# STM32F446RE_board.net
KiCad netlist of a schematic drawn in Altium Designer
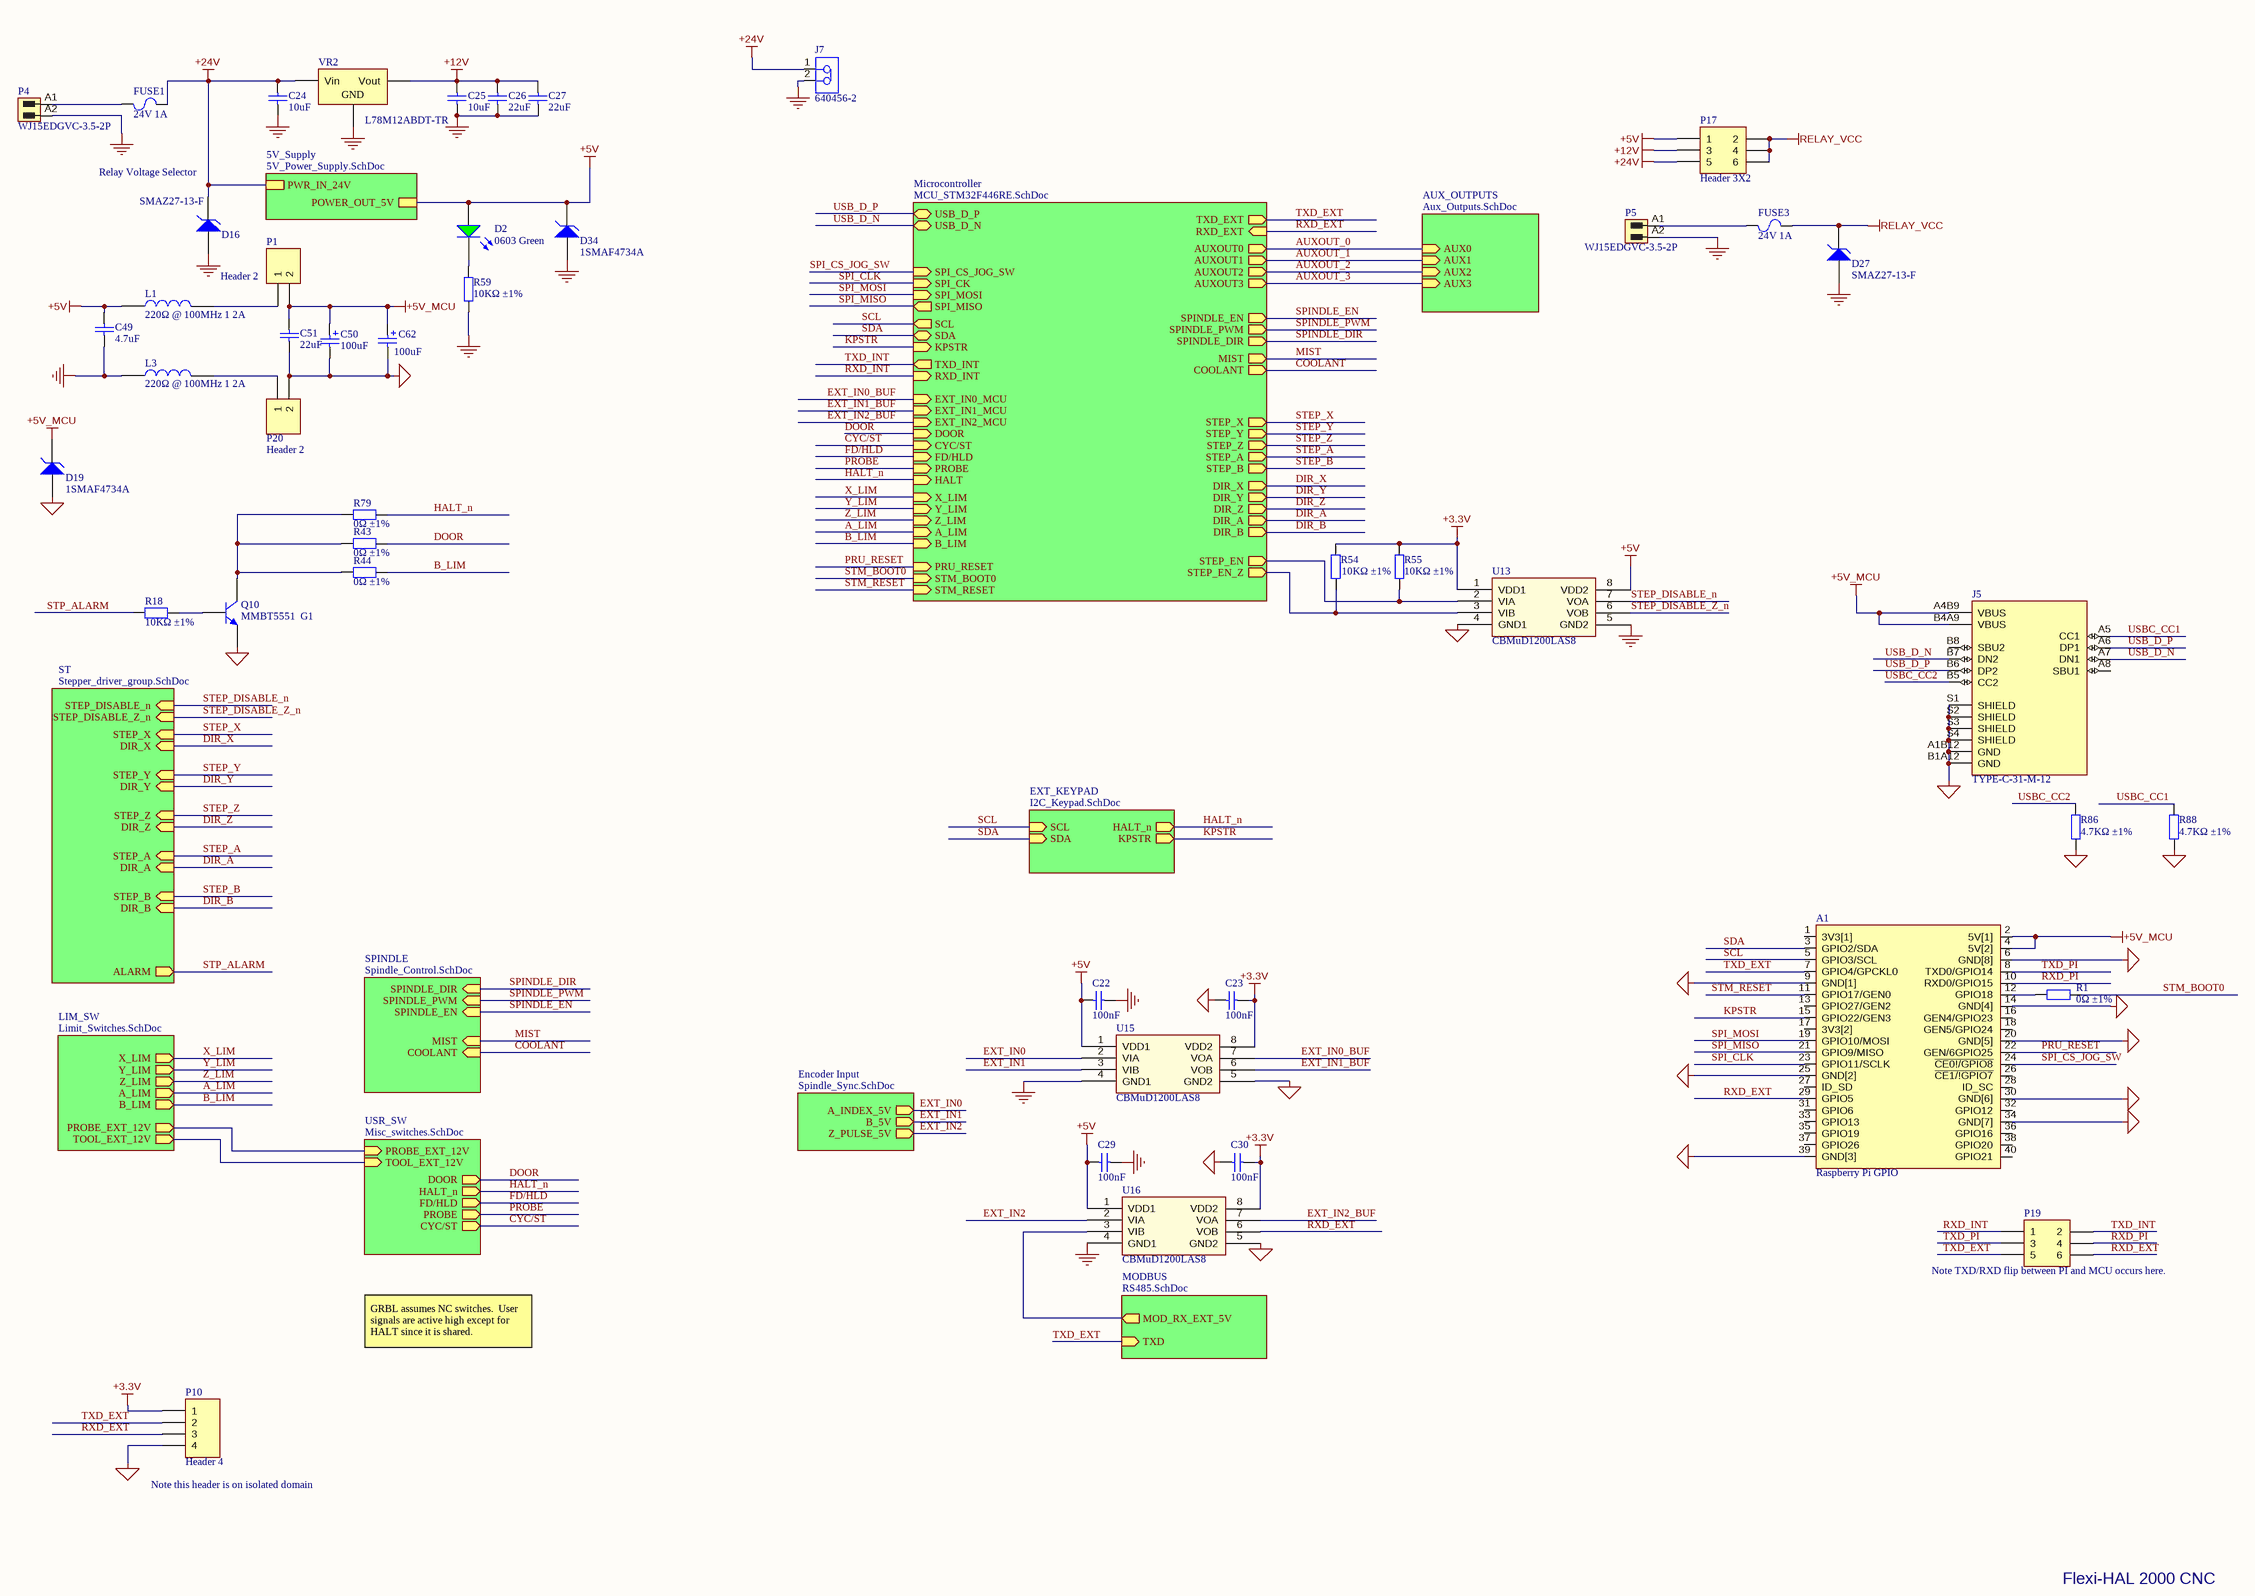
[diagram p0: STM32F446RE_board.SchDoc]

(export (version "E")
  (design (tool "Eeschema 10.0.6"))
  (components
    (comp (ref "A1")
      (value "Raspberry Pi GPIO")
      (footprint "MODULE_RASPBERRY_PI_4_MODEL_B")
      (description "Raspberry Pi Zero WH _Zero W with Headers_")
      (fields (field (name "MP") "DS1023-2*20SF11") (field (name "MF") "CONNFLY Elec"))
      (libsource (lib "Universal_CNC_Breakout") (part "ADA3708"))
    )
    (comp (ref "C22")
      (value "100nF")
      (footprint "0603_C")
      (description "Chip capacitors")
      (fields (field (name "MANUFACTURER") "YAGEO") (field (name "PARTNUMBER") "CC0603KRX7R9BB104"))
      (libsource (lib "Cap") (part "0603 100nF (104) 10% 50V"))
    )
    (comp (ref "C23")
      (value "100nF")
      (footprint "0603_C")
      (description "Chip capacitors")
      (fields (field (name "MANUFACTURER") "YAGEO") (field (name "PARTNUMBER") "CC0603KRX7R9BB104"))
      (libsource (lib "Cap") (part "0603 100nF (104) 10% 50V"))
    )
    (comp (ref "C24")
      (value "10uF")
      (footprint "1206_C")
      (description "Chip capacitors")
      (fields
        (field (name "MANUFACTURER") "Samsung Electro-Mechanics")
        (field (name "PARTNUMBER") "CL31A106KBHNNNE")
      )
      (libsource (lib "Cap") (part "1206 10uF (106) 10% 50V"))
    )
    (comp (ref "C25")
      (value "10uF")
      (footprint "1206_C")
      (description "Chip capacitors")
      (fields
        (field (name "MANUFACTURER") "Samsung Electro-Mechanics")
        (field (name "PARTNUMBER") "CL31A106KBHNNNE")
      )
      (libsource (lib "Cap") (part "1206 10uF (106) 10% 50V"))
    )
    (comp (ref "C26")
      (value "22uF")
      (footprint "0805_C")
      (description "Chip capacitors")
      (fields
        (field (name "MANUFACTURER") "Samsung Electro-Mechanics")
        (field (name "PARTNUMBER") "CL21A226MAQNNNE")
      )
      (libsource (lib "Cap") (part "0805 22uF (226) 20% 25V"))
    )
    (comp (ref "C27")
      (value "22uF")
      (footprint "0805_C")
      (description "Chip capacitors")
      (fields
        (field (name "MANUFACTURER") "Samsung Electro-Mechanics")
        (field (name "PARTNUMBER") "CL21A226MAQNNNE")
      )
      (libsource (lib "Cap") (part "0805 22uF (226) 20% 25V"))
    )
    (comp (ref "C29")
      (value "100nF")
      (footprint "0603_C")
      (description "Chip capacitors")
      (fields (field (name "MANUFACTURER") "YAGEO") (field (name "PARTNUMBER") "CC0603KRX7R9BB104"))
      (libsource (lib "Cap") (part "0603 100nF (104) 10% 50V"))
    )
    (comp (ref "C30")
      (value "100nF")
      (footprint "0603_C")
      (description "Chip capacitors")
      (fields (field (name "MANUFACTURER") "YAGEO") (field (name "PARTNUMBER") "CC0603KRX7R9BB104"))
      (libsource (lib "Cap") (part "0603 100nF (104) 10% 50V"))
    )
    (comp (ref "C49")
      (value "4.7uF")
      (footprint "0603_C")
      (description "Chip capacitors")
      (fields
        (field (name "MANUFACTURER") "Samsung Electro-Mechanics")
        (field (name "PARTNUMBER") "CL10A475KO8NNNC")
      )
      (libsource (lib "Cap") (part "0603 4.7uF (475) 10% 16V"))
    )
    (comp (ref "C50")
      (value "100uF")
      (footprint "CASE-B_3528")
      (description "Tantalum capacitor")
      (fields (field (name "MANUFACTURER") "AVX") (field (name "PARTNUMBER") "TAJB107K006RNJ"))
      (libsource (lib "Cap") (part "3528 100uF (107) 10% 6.3V"))
    )
    (comp (ref "C51")
      (value "22uF")
      (footprint "0805_C")
      (description "Chip capacitors")
      (fields
        (field (name "MANUFACTURER") "Samsung Electro-Mechanics")
        (field (name "PARTNUMBER") "CL21A226MAQNNNE")
      )
      (libsource (lib "Cap") (part "0805 22uF (226) 20% 25V"))
    )
    (comp (ref "C62")
      (value "100uF")
      (footprint "WCAP-ASLI_D6.3H7.7")
      (fields (field (name "MANUFACTURER") "Capxon International Elec"))
      (libsource (lib "IQAnalog") (part "865080445010"))
    )
    (comp (ref "D2")
      (value "0603 Green")
      (footprint "0603_LED_S1")
      (description "LED")
      (libsource (lib "LED") (part "0603 LED Green"))
    )
    (comp (ref "D16")
      (value "SMAZ27-13-F")
      (footprint "DIOM5226X240N")
      (description "27V ±5% 1W 500nA @ 20.5V SMA(DO-214AC) Zener Diodes RoHS")
      (libsource (lib "PrintNC_GRBLHAL_Breakout") (part "BZT52C27"))
    )
    (comp (ref "D19")
      (value "1SMAF4734A")
      (footprint "DIOM5226X240N")
      (description "27V ±5% 1W 500nA @ 20.5V SMA(DO-214AC) Zener Diodes RoHS")
      (libsource (lib "PrintNC_GRBLHAL_Breakout") (part "BZT52C27"))
    )
    (comp (ref "D27")
      (value "SMAZ27-13-F")
      (footprint "DIOM5226X240N")
      (description "27V ±5% 1W 500nA @ 20.5V SMA(DO-214AC) Zener Diodes RoHS")
      (libsource (lib "PrintNC_GRBLHAL_Breakout") (part "BZT52C27"))
    )
    (comp (ref "D34")
      (value "1SMAF4734A")
      (footprint "DIOM5226X240N")
      (description "27V ±5% 1W 500nA @ 20.5V SMA(DO-214AC) Zener Diodes RoHS")
      (libsource (lib "PrintNC_GRBLHAL_Breakout") (part "BZT52C27"))
    )
    (comp (ref "FUSE1")
      (value "24V 1A")
      (footprint "1206_C")
      (description "24V 1A 0.1s 1206 PTC Resettable Fuses RoHS")
      (fields
        (field (name "MANUFACTURER") "Jinrui Electronic Materials Co.")
        (field (name "PARTNUMBER") "JK-nSMD050-24")
      )
      (libsource (lib "PrintNC_GRBLHAL_Breakout") (part "JK-nSMD050-24"))
    )
    (comp (ref "FUSE3")
      (value "24V 1A")
      (footprint "1206_C")
      (description "24V 1A 0.1s 1206 PTC Resettable Fuses RoHS")
      (fields
        (field (name "MANUFACTURER") "Jinrui Electronic Materials Co.")
        (field (name "PARTNUMBER") "JK-nSMD050-24")
      )
      (libsource (lib "PrintNC_GRBLHAL_Breakout") (part "JK-nSMD050-24"))
    )
    (comp (ref "J5")
      (value "TYPE-C-31-M-12")
      (footprint "HRO_TYPE-C-31-M-12")
      (description "USB Connectors 24 Receptacle 1 8.94*7.3mm RoHS")
      (fields (field (name "MF") "HRO Electronics Co., Ltd."))
      (libsource (lib "Universal_CNC_Breakout") (part "TYPE-C-31-M-12"))
    )
    (comp (ref "J7")
      (value "640456-2")
      (footprint "TECO-640456-2_V")
      (fields (field (name "MANUFACTURER") "TE Connectivity"))
      (libsource (lib "Altium Content Vault") (part "CN-2P-F-QF2"))
    )
    (comp (ref "L1")
      (value "220Ω @ 100MHz 1 2A")
      (footprint "0805_C")
      (description "220Ω @ 100MHz 1 2A 150mΩ 0805 Ferrite Beads ROHS")
      (libsource (lib "FBEAD") (part "0402 220R@100Mhz 0.1A"))
    )
    (comp (ref "L3")
      (value "220Ω @ 100MHz 1 2A")
      (footprint "0805_C")
      (description "220Ω @ 100MHz 1 2A 150mΩ 0805 Ferrite Beads ROHS")
      (libsource (lib "FBEAD") (part "0402 220R@100Mhz 0.1A"))
    )
    (comp (ref "P1")
      (value "Header 2")
      (footprint "HDR1X2")
      (description "Header, 2-Pin")
      (fields (field (name "PUBLISHER") "Altium Limited"))
      (libsource (lib "") (part "Header 2_1"))
    )
    (comp (ref "P4")
      (value "WJ15EDGVC-3.5-2P")
      (footprint "691321100002")
      (libsource (lib "Universal_CNC_Breakout") (part "3.5mm Terminal Header 2p"))
    )
    (comp (ref "P5")
      (value "WJ15EDGVC-3.5-2P")
      (footprint "691321100002")
      (fields (field (name "MANUFACTURER") "Weidmueller"))
      (libsource (lib "Universal_CNC_Breakout") (part "3.5mm Terminal Header 2p"))
    )
    (comp (ref "P10")
      (value "Header 4")
      (footprint "HDR1X4")
      (description "Header, 4-Pin")
      (libsource (lib "Miscellaneous Connectors") (part "Header 4"))
    )
    (comp (ref "P17")
      (value "Header 3X2")
      (footprint "HDR2X3")
      (description "Header, 3-Pin, Dual row")
      (fields (field (name "PUBLISHER") "Altium Limited"))
      (libsource (lib "Miscellaneous Connectors") (part "Header 3X2"))
    )
    (comp (ref "P19")
      (value "Header 3X2")
      (footprint "HDR2X3")
      (description "Header, 3-Pin, Dual row")
      (fields (field (name "PUBLISHER") "Altium Limited"))
      (libsource (lib "Miscellaneous Connectors") (part "Header 3X2"))
    )
    (comp (ref "P20")
      (value "Header 2")
      (footprint "HDR1X2")
      (description "Header, 2-Pin")
      (fields (field (name "PUBLISHER") "Altium Limited"))
      (libsource (lib "Miscellaneous Connectors") (part "Header 2"))
    )
    (comp (ref "Q10")
      (value "MMBT5551  G1")
      (footprint "SOT-23(SOT-23-3)")
      (description "三极管")
      (libsource (lib "PrintNC_GRBLHAL_Breakout") (part "SOT-23 MMBT5551  G1"))
    )
    (comp (ref "R1")
      (value "0Ω ±1%")
      (footprint "0603_R")
      (description "Chip resistor")
      (fields (field (name "MANUFACTURER") "Uniroyal Elec") (field (name "PARTNUMBER") "0603WAF0000T5E"))
      (libsource (lib "RES") (part "0603 0R (0R0) 1%"))
    )
    (comp (ref "R18")
      (value "10KΩ ±1%")
      (footprint "0603_R")
      (description "Chip resistor")
      (fields (field (name "MANUFACTURER") "Uniroyal Elec") (field (name "PARTNUMBER") "0603WAF1002T5E"))
      (libsource (lib "") (part "0603 10K (1002) 1%_2"))
    )
    (comp (ref "R43")
      (value "0Ω ±1%")
      (footprint "0603_R")
      (description "Chip resistor")
      (fields (field (name "MANUFACTURER") "Uniroyal Elec") (field (name "PARTNUMBER") "0603WAF0000T5E"))
      (libsource (lib "RES") (part "0603 0R (0R0) 1%"))
    )
    (comp (ref "R44")
      (value "0Ω ±1%")
      (footprint "0603_R")
      (description "Chip resistor")
      (fields (field (name "MANUFACTURER") "Uniroyal Elec") (field (name "PARTNUMBER") "0603WAF0000T5E"))
      (libsource (lib "RES") (part "0603 0R (0R0) 1%"))
    )
    (comp (ref "R54")
      (value "10KΩ ±1%")
      (footprint "0603_R")
      (description "Chip resistor")
      (fields (field (name "MANUFACTURER") "Uniroyal Elec") (field (name "PARTNUMBER") "0603WAF1002T5E"))
      (libsource (lib "RES") (part "0603 10K (1002) 1%"))
    )
    (comp (ref "R55")
      (value "10KΩ ±1%")
      (footprint "0603_R")
      (description "Chip resistor")
      (fields (field (name "MANUFACTURER") "Uniroyal Elec") (field (name "PARTNUMBER") "0603WAF1002T5E"))
      (libsource (lib "RES") (part "0603 10K (1002) 1%"))
    )
    (comp (ref "R59")
      (value "10KΩ ±1%")
      (footprint "0603_R")
      (description "Chip resistor")
      (fields (field (name "MANUFACTURER") "Uniroyal Elec") (field (name "PARTNUMBER") "0603WAF1002T5E"))
      (libsource (lib "") (part "0603 10K (1002) 1%_1"))
    )
    (comp (ref "R79")
      (value "0Ω ±1%")
      (footprint "0603_R")
      (description "Chip resistor")
      (fields (field (name "MANUFACTURER") "Uniroyal Elec") (field (name "PARTNUMBER") "0603WAF0000T5E"))
      (libsource (lib "RES") (part "0603 0R (0R0) 1%"))
    )
    (comp (ref "R86")
      (value "4.7KΩ ±1%")
      (footprint "0603_R")
      (description "Chip resistor")
      (fields (field (name "MANUFACTURER") "Uniroyal Elec") (field (name "PARTNUMBER") "0603WAF4701T5E"))
      (libsource (lib "RES") (part "0603 4.7K (4701) 1%"))
    )
    (comp (ref "R88")
      (value "4.7KΩ ±1%")
      (footprint "0603_R")
      (description "Chip resistor")
      (fields (field (name "MANUFACTURER") "Uniroyal Elec") (field (name "PARTNUMBER") "0603WAF4701T5E"))
      (libsource (lib "RES") (part "0603 4.7K (4701) 1%"))
    )
    (comp (ref "U13")
      (value "CBMuD1200LAS8")
      (footprint "SOIC-8_150mil")
      (description "Dual Channel Isolator")
      (libsource (lib "IC") (part "CBMuD1200LAS8"))
    )
    (comp (ref "U15")
      (value "CBMuD1200LAS8")
      (footprint "SOIC-8_150mil")
      (description "Dual Channel Isolator")
      (libsource (lib "IC") (part "CBMuD1200LAS8"))
    )
    (comp (ref "U16")
      (value "CBMuD1200LAS8")
      (footprint "SOIC-8_150mil")
      (description "Dual Channel Isolator")
      (libsource (lib "IC") (part "CBMuD1200LAS8"))
    )
    (comp (ref "VR2")
      (value "L78M12ABDT-TR")
      (footprint "TO-252-2-180")
      (libsource (lib "PrintNC_GRBLHAL_Breakout") (part "TO-252-2 L78M05ABDT-TR"))
    )
  )
  (nets
    (net (code "1") (name "+3.3V") (class "Default")
      (node (ref "C23") (pin "2") (pinfunction "2_2") (pintype "passive"))
      (node (ref "C30") (pin "2") (pinfunction "2_2") (pintype "passive"))
      (node (ref "P10") (pin "1") (pinfunction "1_1") (pintype "passive"))
      (node (ref "R54") (pin "1") (pinfunction "1_1") (pintype "passive"))
      (node (ref "R55") (pin "1") (pinfunction "1_1") (pintype "passive"))
      (node (ref "U13") (pin "1") (pinfunction "VDD1_1") (pintype "passive"))
      (node (ref "U15") (pin "8") (pinfunction "VDD2_8") (pintype "passive"))
      (node (ref "U16") (pin "8") (pinfunction "VDD2_8") (pintype "passive"))
    )
    (net (code "2") (name "+5V") (class "Default")
      (node (ref "C22") (pin "1") (pinfunction "1_1") (pintype "passive"))
      (node (ref "C29") (pin "1") (pinfunction "1_1") (pintype "passive"))
      (node (ref "C49") (pin "2") (pinfunction "2_2") (pintype "passive"))
      (node (ref "D2") (pin "A") (pinfunction "A_A") (pintype "passive"))
      (node (ref "D34") (pin "2") (pinfunction "K_2") (pintype "passive"))
      (node (ref "L1") (pin "1") (pinfunction "1_1") (pintype "passive"))
      (node (ref "P17") (pin "1") (pinfunction "1_1") (pintype "passive"))
      (node (ref "U13") (pin "8") (pinfunction "VDD2_8") (pintype "passive"))
      (node (ref "U15") (pin "1") (pinfunction "VDD1_1") (pintype "passive"))
      (node (ref "U16") (pin "1") (pinfunction "VDD1_1") (pintype "passive"))
    )
    (net (code "3") (name "+5V_MCU") (class "Default")
      (node (ref "A1") (pin "2") (pinfunction "5V[1]_2") (pintype "power_in"))
      (node (ref "A1") (pin "4") (pinfunction "5V[2]_4") (pintype "power_in"))
      (node (ref "C50") (pin "1") (pinfunction "1_1") (pintype "passive"))
      (node (ref "C51") (pin "2") (pinfunction "2_2") (pintype "passive"))
      (node (ref "C62") (pin "1") (pinfunction "P_1") (pintype "passive"))
      (node (ref "D19") (pin "2") (pinfunction "K_2") (pintype "passive"))
      (node (ref "J5") (pin "A4B9") (pinfunction "VBUS_A4B9") (pintype "power_in"))
      (node (ref "J5") (pin "B4A9") (pinfunction "VBUS_B4A9") (pintype "power_in"))
      (node (ref "P1") (pin "2") (pinfunction "2_2") (pintype "passive"))
    )
    (net (code "4") (name "+12V") (class "Default")
      (node (ref "C25") (pin "2") (pinfunction "2_2") (pintype "passive"))
      (node (ref "C26") (pin "2") (pinfunction "2_2") (pintype "passive"))
      (node (ref "C27") (pin "2") (pinfunction "2_2") (pintype "passive"))
      (node (ref "P17") (pin "3") (pinfunction "3_3") (pintype "passive"))
      (node (ref "VR2") (pin "3") (pinfunction "Vout_3") (pintype "passive"))
    )
    (net (code "5") (name "+24V") (class "Default")
      (node (ref "C24") (pin "2") (pinfunction "2_2") (pintype "passive"))
      (node (ref "D16") (pin "2") (pinfunction "K_2") (pintype "passive"))
      (node (ref "FUSE1") (pin "2") (pinfunction "2_2") (pintype "passive"))
      (node (ref "J7") (pin "1") (pinfunction "1_1") (pintype "passive"))
      (node (ref "P17") (pin "5") (pinfunction "5_5") (pintype "passive"))
      (node (ref "VR2") (pin "1") (pinfunction "Vin_1") (pintype "passive"))
    )
    (net (code "11") (name "/B_LIM") (class "Default")
      (node (ref "R44") (pin "1") (pinfunction "1_1") (pintype "passive"))
    )
    (net (code "19") (name "/DOOR") (class "Default")
      (node (ref "R43") (pin "1") (pinfunction "1_1") (pintype "passive"))
    )
    (net (code "20") (name "/EXT_IN0") (class "Default")
      (node (ref "U15") (pin "2") (pinfunction "VIA_2") (pintype "passive"))
    )
    (net (code "21") (name "/EXT_IN0_BUF") (class "Default")
      (node (ref "U15") (pin "7") (pinfunction "VOA_7") (pintype "passive"))
    )
    (net (code "22") (name "/EXT_IN1") (class "Default")
      (node (ref "U15") (pin "3") (pinfunction "VIB_3") (pintype "passive"))
    )
    (net (code "23") (name "/EXT_IN1_BUF") (class "Default")
      (node (ref "U15") (pin "6") (pinfunction "VOB_6") (pintype "passive"))
    )
    (net (code "24") (name "/EXT_IN2") (class "Default")
      (node (ref "U16") (pin "2") (pinfunction "VIA_2") (pintype "passive"))
    )
    (net (code "25") (name "/EXT_IN2_BUF") (class "Default")
      (node (ref "U16") (pin "7") (pinfunction "VOA_7") (pintype "passive"))
    )
    (net (code "27") (name "/HALT_n") (class "Default")
      (node (ref "R79") (pin "1") (pinfunction "1_1") (pintype "passive"))
    )
    (net (code "28") (name "/KPSTR") (class "Default")
      (node (ref "A1") (pin "15") (pinfunction "GPIO22/GEN3_15") (pintype "bidirectional"))
    )
    (net (code "30") (name "/MOD_RX_EXT_5V") (class "Default")
      (node (ref "U16") (pin "3") (pinfunction "VIB_3") (pintype "passive"))
    )
    (net (code "33") (name "/PRU_RESET") (class "Default")
      (node (ref "A1") (pin "22") (pinfunction "GEN/6GPIO25_22") (pintype "bidirectional"))
    )
    (net (code "34") (name "/RXD_EXT") (class "Default")
      (node (ref "A1") (pin "29") (pinfunction "GPIO5_29") (pintype "bidirectional"))
      (node (ref "P10") (pin "3") (pinfunction "3_3") (pintype "passive"))
      (node (ref "P19") (pin "6") (pinfunction "6_6") (pintype "passive"))
      (node (ref "U16") (pin "6") (pinfunction "VOB_6") (pintype "passive"))
    )
    (net (code "35") (name "/RXD_INT") (class "Default")
      (node (ref "P19") (pin "1") (pinfunction "1_1") (pintype "passive"))
    )
    (net (code "36") (name "/RXD_PI") (class "Default")
      (node (ref "A1") (pin "10") (pinfunction "RXD0/GPIO15_10") (pintype "bidirectional"))
      (node (ref "P19") (pin "4") (pinfunction "4_4") (pintype "passive"))
    )
    (net (code "37") (name "/SCL") (class "Default")
      (node (ref "A1") (pin "5") (pinfunction "GPIO3/SCL_5") (pintype "bidirectional"))
    )
    (net (code "38") (name "/SDA") (class "Default")
      (node (ref "A1") (pin "3") (pinfunction "GPIO2/SDA_3") (pintype "bidirectional"))
    )
    (net (code "42") (name "/SPI_CLK") (class "Default")
      (node (ref "A1") (pin "23") (pinfunction "GPIO11/SCLK_23") (pintype "bidirectional"))
    )
    (net (code "43") (name "/SPI_CS_JOG_SW") (class "Default")
      (node (ref "A1") (pin "24") (pinfunction "~{CE0!/GPIO8}_24") (pintype "bidirectional"))
    )
    (net (code "44") (name "/SPI_MISO") (class "Default")
      (node (ref "A1") (pin "21") (pinfunction "GPIO9/MISO_21") (pintype "bidirectional"))
    )
    (net (code "45") (name "/SPI_MOSI") (class "Default")
      (node (ref "A1") (pin "19") (pinfunction "GPIO10/MOSI_19") (pintype "bidirectional"))
    )
    (net (code "48") (name "/STEP_DISABLE_Z_n") (class "Default")
      (node (ref "U13") (pin "6") (pinfunction "VOB_6") (pintype "passive"))
    )
    (net (code "49") (name "/STEP_DISABLE_n") (class "Default")
      (node (ref "U13") (pin "7") (pinfunction "VOA_7") (pintype "passive"))
    )
    (net (code "50") (name "/STEP_EN") (class "Default")
      (node (ref "R55") (pin "2") (pinfunction "2_2") (pintype "passive"))
      (node (ref "U13") (pin "2") (pinfunction "VIA_2") (pintype "passive"))
    )
    (net (code "51") (name "/STEP_EN_Z") (class "Default")
      (node (ref "R54") (pin "2") (pinfunction "2_2") (pintype "passive"))
      (node (ref "U13") (pin "3") (pinfunction "VIB_3") (pintype "passive"))
    )
    (net (code "55") (name "/STM_BOOT0") (class "Default")
      (node (ref "R1") (pin "1") (pinfunction "1_1") (pintype "passive"))
    )
    (net (code "56") (name "/STM_RESET") (class "Default")
      (node (ref "A1") (pin "11") (pinfunction "GPIO17/GEN0_11") (pintype "bidirectional"))
    )
    (net (code "57") (name "/STP_ALARM") (class "Default")
      (node (ref "R18") (pin "2") (pinfunction "2_2") (pintype "passive"))
    )
    (net (code "59") (name "/TXD_EXT") (class "Default")
      (node (ref "A1") (pin "7") (pinfunction "GPIO4/GPCKL0_7") (pintype "bidirectional"))
      (node (ref "P10") (pin "2") (pinfunction "2_2") (pintype "passive"))
      (node (ref "P19") (pin "5") (pinfunction "5_5") (pintype "passive"))
    )
    (net (code "60") (name "/TXD_INT") (class "Default")
      (node (ref "P19") (pin "2") (pinfunction "2_2") (pintype "passive"))
    )
    (net (code "61") (name "/TXD_PI") (class "Default")
      (node (ref "A1") (pin "8") (pinfunction "TXD0/GPIO14_8") (pintype "bidirectional"))
      (node (ref "P19") (pin "3") (pinfunction "3_3") (pintype "passive"))
    )
    (net (code "62") (name "/USBC_CC1") (class "Default")
      (node (ref "J5") (pin "A5") (pinfunction "CC1_A5") (pintype "bidirectional"))
      (node (ref "R88") (pin "1") (pinfunction "1_1") (pintype "passive"))
    )
    (net (code "63") (name "/USBC_CC2") (class "Default")
      (node (ref "J5") (pin "B5") (pinfunction "CC2_B5") (pintype "bidirectional"))
      (node (ref "R86") (pin "1") (pinfunction "1_1") (pintype "passive"))
    )
    (net (code "64") (name "/USB_D_N") (class "Default")
      (node (ref "J5") (pin "A7") (pinfunction "DN1_A7") (pintype "bidirectional"))
      (node (ref "J5") (pin "B7") (pinfunction "DN2_B7") (pintype "bidirectional"))
    )
    (net (code "65") (name "/USB_D_P") (class "Default")
      (node (ref "J5") (pin "A6") (pinfunction "DP1_A6") (pintype "bidirectional"))
      (node (ref "J5") (pin "B6") (pinfunction "DP2_B6") (pintype "bidirectional"))
    )
    (net (code "69") (name "GND") (class "Default")
      (node (ref "C22") (pin "2") (pinfunction "2_2") (pintype "passive"))
      (node (ref "C24") (pin "1") (pinfunction "1_1") (pintype "passive"))
      (node (ref "C25") (pin "1") (pinfunction "1_1") (pintype "passive"))
      (node (ref "C26") (pin "1") (pinfunction "1_1") (pintype "passive"))
      (node (ref "C27") (pin "1") (pinfunction "1_1") (pintype "passive"))
      (node (ref "C29") (pin "2") (pinfunction "2_2") (pintype "passive"))
      (node (ref "C49") (pin "1") (pinfunction "1_1") (pintype "passive"))
      (node (ref "D16") (pin "1") (pinfunction "A_1") (pintype "passive"))
      (node (ref "D27") (pin "1") (pinfunction "A_1") (pintype "passive"))
      (node (ref "D34") (pin "1") (pinfunction "A_1") (pintype "passive"))
      (node (ref "J7") (pin "2") (pinfunction "2_2") (pintype "passive"))
      (node (ref "L3") (pin "1") (pinfunction "1_1") (pintype "passive"))
      (node (ref "P4") (pin "A2") (pinfunction "A2_A2") (pintype "passive"))
      (node (ref "P5") (pin "A2") (pinfunction "A2_A2") (pintype "passive"))
      (node (ref "R59") (pin "1") (pinfunction "1_1") (pintype "passive"))
      (node (ref "U13") (pin "5") (pinfunction "GND2_5") (pintype "passive"))
      (node (ref "U15") (pin "4") (pinfunction "GND1_4") (pintype "passive"))
      (node (ref "U16") (pin "4") (pinfunction "GND1_4") (pintype "passive"))
      (node (ref "VR2") (pin "2") (pinfunction "GND_2") (pintype "passive"))
    )
    (net (code "70") (name "MCU_GND") (class "Default")
      (node (ref "A1") (pin "14") (pinfunction "GND[4]_14") (pintype "power_in"))
      (node (ref "A1") (pin "20") (pinfunction "GND[5]_20") (pintype "power_in"))
      (node (ref "A1") (pin "25") (pinfunction "GND[2]_25") (pintype "power_in"))
      (node (ref "A1") (pin "30") (pinfunction "GND[6]_30") (pintype "power_in"))
      (node (ref "A1") (pin "34") (pinfunction "GND[7]_34") (pintype "power_in"))
      (node (ref "A1") (pin "39") (pinfunction "GND[3]_39") (pintype "power_in"))
      (node (ref "A1") (pin "6") (pinfunction "GND[8]_6") (pintype "power_in"))
      (node (ref "A1") (pin "9") (pinfunction "GND[1]_9") (pintype "power_in"))
      (node (ref "C23") (pin "1") (pinfunction "1_1") (pintype "passive"))
      (node (ref "C30") (pin "1") (pinfunction "1_1") (pintype "passive"))
      (node (ref "C50") (pin "2") (pinfunction "2_2") (pintype "passive"))
      (node (ref "C51") (pin "1") (pinfunction "1_1") (pintype "passive"))
      (node (ref "C62") (pin "2") (pinfunction "N_2") (pintype "passive"))
      (node (ref "D19") (pin "1") (pinfunction "A_1") (pintype "passive"))
      (node (ref "J5") (pin "A1B12") (pinfunction "GND_A1B12") (pintype "power_in"))
      (node (ref "J5") (pin "B1A12") (pinfunction "GND_B1A12") (pintype "power_in"))
      (node (ref "J5") (pin "S1") (pinfunction "SHIELD_S1") (pintype "passive"))
      (node (ref "J5") (pin "S2") (pinfunction "SHIELD_S2") (pintype "passive"))
      (node (ref "J5") (pin "S3") (pinfunction "SHIELD_S3") (pintype "passive"))
      (node (ref "J5") (pin "S4") (pinfunction "SHIELD_S4") (pintype "passive"))
      (node (ref "P10") (pin "4") (pinfunction "4_4") (pintype "passive"))
      (node (ref "P20") (pin "2") (pinfunction "2_2") (pintype "passive"))
      (node (ref "Q10") (pin "2") (pinfunction "E_2") (pintype "passive"))
      (node (ref "R86") (pin "2") (pinfunction "2_2") (pintype "passive"))
      (node (ref "R88") (pin "2") (pinfunction "2_2") (pintype "passive"))
      (node (ref "U13") (pin "4") (pinfunction "GND1_4") (pintype "passive"))
      (node (ref "U15") (pin "5") (pinfunction "GND2_5") (pintype "passive"))
      (node (ref "U16") (pin "5") (pinfunction "GND2_5") (pintype "passive"))
    )
    (net (code "71") (name "Net-(A1-GPIO18)") (class "Default")
      (node (ref "A1") (pin "12") (pinfunction "GPIO18_12") (pintype "bidirectional"))
      (node (ref "R1") (pin "2") (pinfunction "2_2") (pintype "passive"))
    )
    (net (code "72") (name "Net-(D2-PadK)") (class "Default")
      (node (ref "D2") (pin "K") (pinfunction "K_K") (pintype "passive"))
      (node (ref "R59") (pin "2") (pinfunction "2_2") (pintype "passive"))
    )
    (net (code "73") (name "Net-(FUSE1-Pad1)") (class "Default")
      (node (ref "FUSE1") (pin "1") (pinfunction "1_1") (pintype "passive"))
      (node (ref "P4") (pin "A1") (pinfunction "A1_A1") (pintype "passive"))
    )
    (net (code "74") (name "Net-(FUSE3-Pad1)") (class "Default")
      (node (ref "FUSE3") (pin "1") (pinfunction "1_1") (pintype "passive"))
      (node (ref "P5") (pin "A1") (pinfunction "A1_A1") (pintype "passive"))
    )
    (net (code "75") (name "Net-(L1-Pad2)") (class "Default")
      (node (ref "L1") (pin "2") (pinfunction "2_2") (pintype "passive"))
      (node (ref "P1") (pin "1") (pinfunction "1_1") (pintype "passive"))
    )
    (net (code "76") (name "Net-(L3-Pad2)") (class "Default")
      (node (ref "L3") (pin "2") (pinfunction "2_2") (pintype "passive"))
      (node (ref "P20") (pin "1") (pinfunction "1_1") (pintype "passive"))
    )
    (net (code "77") (name "Net-(Q10-B)") (class "Default")
      (node (ref "Q10") (pin "1") (pinfunction "B_1") (pintype "passive"))
      (node (ref "R18") (pin "1") (pinfunction "1_1") (pintype "passive"))
    )
    (net (code "78") (name "Net-(Q10-C)") (class "Default")
      (node (ref "Q10") (pin "3") (pinfunction "C_3") (pintype "passive"))
      (node (ref "R43") (pin "2") (pinfunction "2_2") (pintype "passive"))
      (node (ref "R44") (pin "2") (pinfunction "2_2") (pintype "passive"))
      (node (ref "R79") (pin "2") (pinfunction "2_2") (pintype "passive"))
    )
    (net (code "79") (name "RELAY_VCC") (class "Default")
      (node (ref "D27") (pin "2") (pinfunction "K_2") (pintype "passive"))
      (node (ref "FUSE3") (pin "2") (pinfunction "2_2") (pintype "passive"))
      (node (ref "P17") (pin "2") (pinfunction "2_2") (pintype "passive"))
      (node (ref "P17") (pin "4") (pinfunction "4_4") (pintype "passive"))
      (node (ref "P17") (pin "6") (pinfunction "6_6") (pintype "passive"))
    )
    (net (code "80") (name "unconnected-(A1-3V3[1]-Pad1)") (class "Default")
      (node (ref "A1") (pin "1") (pinfunction "3V3[1]_1") (pintype "power_in"))
    )
    (net (code "81") (name "unconnected-(A1-3V3[2]-Pad17)") (class "Default")
      (node (ref "A1") (pin "17") (pinfunction "3V3[2]_17") (pintype "power_in"))
    )
    (net (code "82") (name "unconnected-(A1-GEN4{slash}GPIO23-Pad16)") (class "Default")
      (node (ref "A1") (pin "16") (pinfunction "GEN4/GPIO23_16") (pintype "bidirectional"))
    )
    (net (code "83") (name "unconnected-(A1-GEN5{slash}GPIO24-Pad18)") (class "Default")
      (node (ref "A1") (pin "18") (pinfunction "GEN5/GPIO24_18") (pintype "bidirectional"))
    )
    (net (code "84") (name "unconnected-(A1-GPIO6-Pad31)") (class "Default")
      (node (ref "A1") (pin "31") (pinfunction "GPIO6_31") (pintype "bidirectional"))
    )
    (net (code "85") (name "unconnected-(A1-GPIO12-Pad32)") (class "Default")
      (node (ref "A1") (pin "32") (pinfunction "GPIO12_32") (pintype "bidirectional"))
    )
    (net (code "86") (name "unconnected-(A1-GPIO13-Pad33)") (class "Default")
      (node (ref "A1") (pin "33") (pinfunction "GPIO13_33") (pintype "bidirectional"))
    )
    (net (code "87") (name "unconnected-(A1-GPIO16-Pad36)") (class "Default")
      (node (ref "A1") (pin "36") (pinfunction "GPIO16_36") (pintype "bidirectional"))
    )
    (net (code "88") (name "unconnected-(A1-GPIO19-Pad35)") (class "Default")
      (node (ref "A1") (pin "35") (pinfunction "GPIO19_35") (pintype "bidirectional"))
    )
    (net (code "89") (name "unconnected-(A1-GPIO20-Pad38)") (class "Default")
      (node (ref "A1") (pin "38") (pinfunction "GPIO20_38") (pintype "bidirectional"))
    )
    (net (code "90") (name "unconnected-(A1-GPIO21-Pad40)") (class "Default")
      (node (ref "A1") (pin "40") (pinfunction "GPIO21_40") (pintype "bidirectional"))
    )
    (net (code "91") (name "unconnected-(A1-GPIO26-Pad37)") (class "Default")
      (node (ref "A1") (pin "37") (pinfunction "GPIO26_37") (pintype "bidirectional"))
    )
    (net (code "92") (name "unconnected-(A1-GPIO27{slash}GEN2-Pad13)") (class "Default")
      (node (ref "A1") (pin "13") (pinfunction "GPIO27/GEN2_13") (pintype "bidirectional"))
    )
    (net (code "93") (name "unconnected-(A1-ID_SC-Pad28)") (class "Default")
      (node (ref "A1") (pin "28") (pinfunction "ID_SC_28") (pintype "bidirectional"))
    )
    (net (code "94") (name "unconnected-(A1-ID_SD-Pad27)") (class "Default")
      (node (ref "A1") (pin "27") (pinfunction "ID_SD_27") (pintype "bidirectional"))
    )
    (net (code "95") (name "unconnected-(A1-~{CE1{slash}!GPIO7}-Pad26)") (class "Default")
      (node (ref "A1") (pin "26") (pinfunction "~{CE1/!GPIO7}_26") (pintype "bidirectional"))
    )
    (net (code "96") (name "unconnected-(J5-SBU1-PadA8)") (class "Default")
      (node (ref "J5") (pin "A8") (pinfunction "SBU1_A8") (pintype "bidirectional"))
    )
    (net (code "97") (name "unconnected-(J5-SBU2-PadB8)") (class "Default")
      (node (ref "J5") (pin "B8") (pinfunction "SBU2_B8") (pintype "bidirectional"))
    )
  )
)
